# PicoCoffeeMachine_2021-02-28.net
KiCad netlist of a schematic drawn in EasyEDA
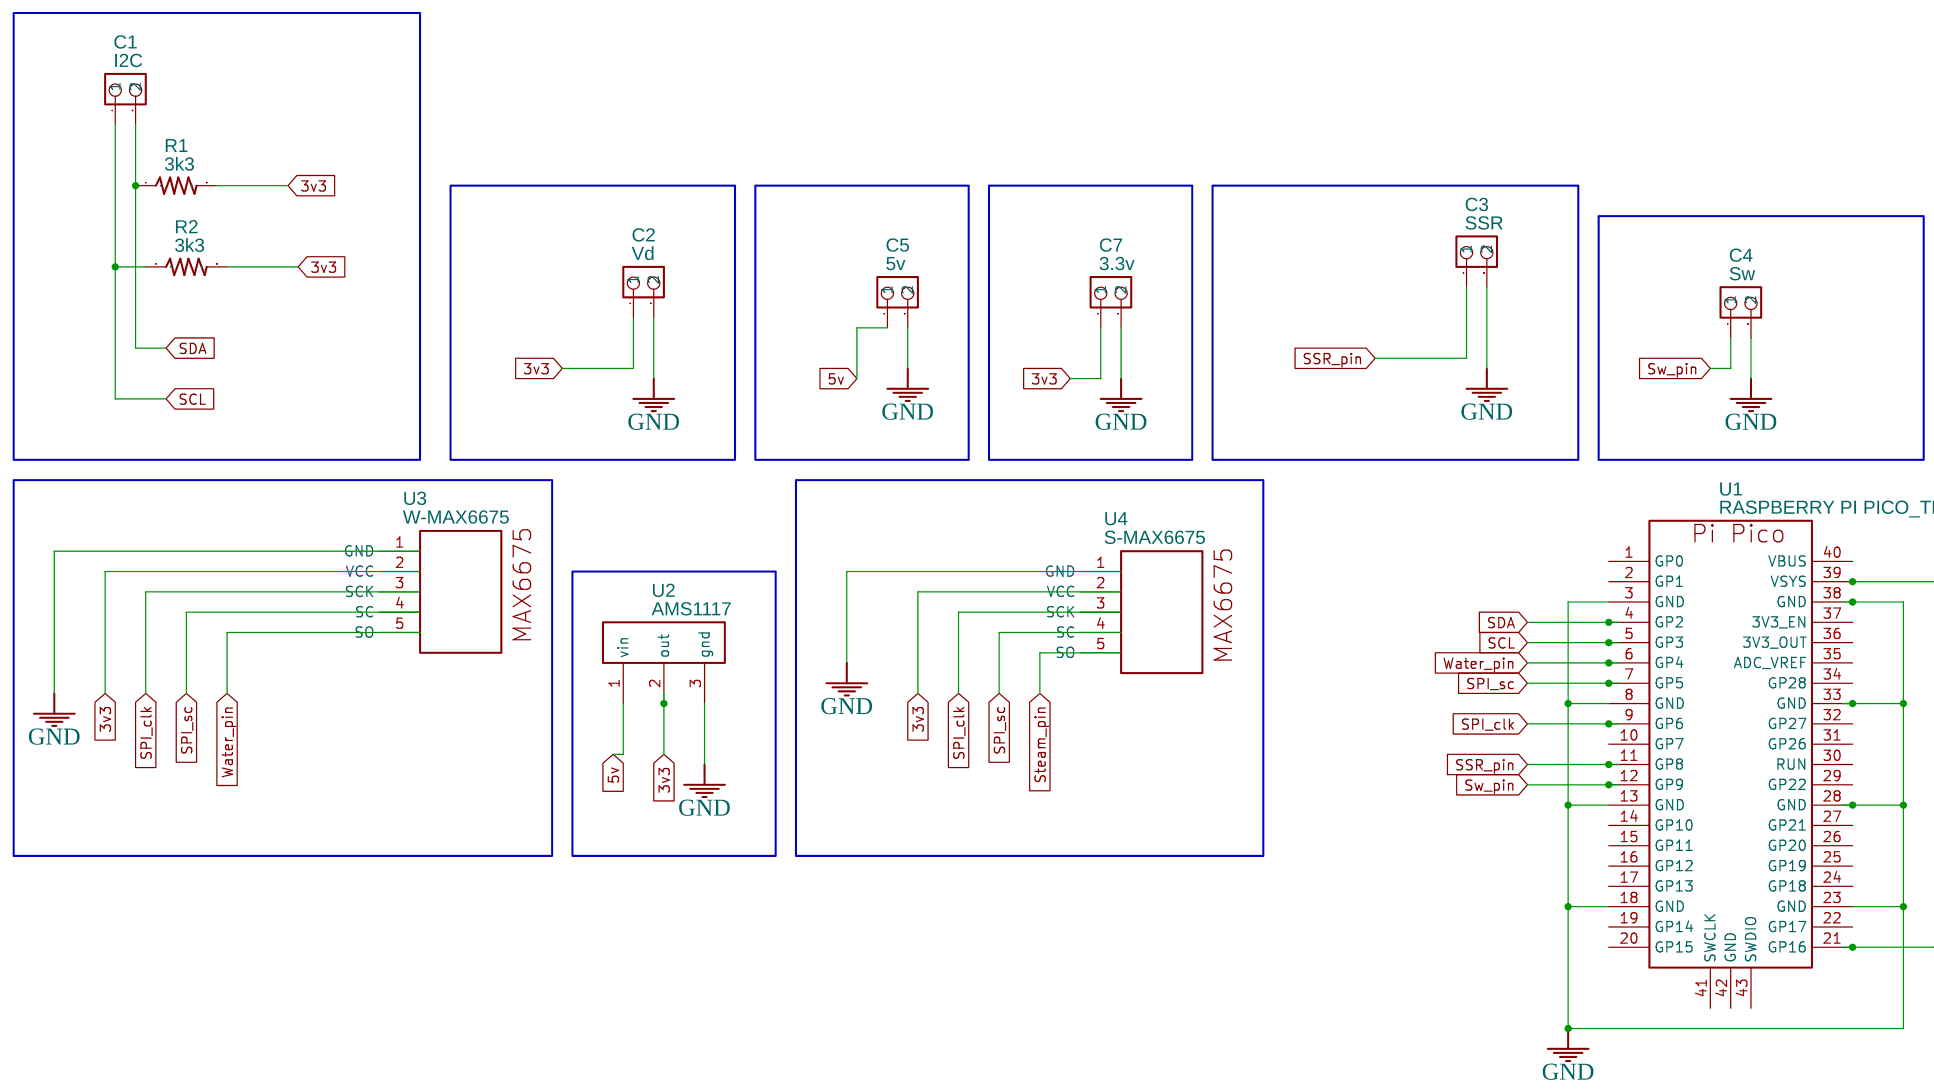
[diagram p0: schematic sheet]

(export (version "E")
  (design (tool "Eeschema 10.0.6"))
  (components
    (comp (ref "C1")
      (value "I2C")
      (fields (field (name "BOM_Manufacturer Part") "XH-2A"))
      (libsource (lib "") (part "JST"))
    )
    (comp (ref "C2")
      (value "Vd")
      (fields (field (name "BOM_Manufacturer Part") "XH-2A"))
      (libsource (lib "") (part "JST"))
    )
    (comp (ref "C3")
      (value "SSR")
      (fields (field (name "BOM_Manufacturer Part") "XH-2A"))
      (libsource (lib "") (part "JST"))
    )
    (comp (ref "C4")
      (value "Sw")
      (fields (field (name "BOM_Manufacturer Part") "XH-2A"))
      (libsource (lib "") (part "JST"))
    )
    (comp (ref "C5")
      (value "5v")
      (fields (field (name "BOM_Manufacturer Part") "XH-2A"))
      (libsource (lib "") (part "JST"))
    )
    (comp (ref "C7")
      (value "3.3v")
      (fields (field (name "BOM_Manufacturer Part") "XH-2A"))
      (libsource (lib "") (part "JST"))
    )
    (comp (ref "R1") (value "3k3") (libsource (lib "") (part "RESISTOR")))
    (comp (ref "R2") (value "3k3") (libsource (lib "") (part "RESISTOR")))
    (comp (ref "U1")
      (value "RASPBERRY PI PICO_THROUGH_HOLE COPY")
      (fields (field (name "BOM_Manufacturer Part") "Pi Pico"))
      (libsource (lib "") (part "RASPBERRY PI PICO_THROUGH_HOLE COPY"))
    )
    (comp (ref "U2") (value "AMS1117") (libsource (lib "") (part "AMS1117")))
    (comp (ref "U3") (value "W-MAX6675") (libsource (lib "") (part "MAX6675")))
    (comp (ref "U4") (value "S-MAX6675") (libsource (lib "") (part "MAX6675")))
  )
  (nets
    (net (code "1") (name "3v3") (class "Default")
      (node (ref "C2") (pin "1") (pinfunction "1_1") (pintype "unspecified"))
      (node (ref "C7") (pin "1") (pinfunction "1_1") (pintype "unspecified"))
      (node (ref "R1") (pin "2") (pinfunction "2_2") (pintype "unspecified"))
      (node (ref "R2") (pin "2") (pinfunction "2_2") (pintype "unspecified"))
      (node (ref "U1") (pin "39") (pinfunction "VSYS_39") (pintype "unspecified"))
      (node (ref "U2") (pin "2") (pinfunction "out_2") (pintype "unspecified"))
      (node (ref "U3") (pin "2") (pinfunction "VCC_2") (pintype "unspecified"))
      (node (ref "U4") (pin "2") (pinfunction "VCC_2") (pintype "unspecified"))
    )
    (net (code "2") (name "5v") (class "Default")
      (node (ref "C5") (pin "1") (pinfunction "1_1") (pintype "unspecified"))
      (node (ref "U2") (pin "1") (pinfunction "vin_1") (pintype "unspecified"))
    )
    (net (code "3") (name "GND") (class "Default")
      (node (ref "C2") (pin "2") (pinfunction "2_2") (pintype "unspecified"))
      (node (ref "C3") (pin "2") (pinfunction "2_2") (pintype "unspecified"))
      (node (ref "C4") (pin "2") (pinfunction "2_2") (pintype "unspecified"))
      (node (ref "C5") (pin "2") (pinfunction "2_2") (pintype "unspecified"))
      (node (ref "C7") (pin "2") (pinfunction "2_2") (pintype "unspecified"))
      (node (ref "U1") (pin "13") (pinfunction "GND_13") (pintype "unspecified"))
      (node (ref "U1") (pin "18") (pinfunction "GND_18") (pintype "unspecified"))
      (node (ref "U1") (pin "23") (pinfunction "GND_23") (pintype "unspecified"))
      (node (ref "U1") (pin "28") (pinfunction "GND_28") (pintype "unspecified"))
      (node (ref "U1") (pin "3") (pinfunction "GND_3") (pintype "unspecified"))
      (node (ref "U1") (pin "33") (pinfunction "GND_33") (pintype "unspecified"))
      (node (ref "U1") (pin "38") (pinfunction "GND_38") (pintype "unspecified"))
      (node (ref "U1") (pin "8") (pinfunction "GND_8") (pintype "unspecified"))
      (node (ref "U2") (pin "3") (pinfunction "gnd_3") (pintype "unspecified"))
      (node (ref "U3") (pin "1") (pinfunction "GND_1") (pintype "unspecified"))
      (node (ref "U4") (pin "1") (pinfunction "GND_1") (pintype "unspecified"))
    )
    (net (code "4") (name "SCL") (class "Default")
      (node (ref "C1") (pin "1") (pinfunction "1_1") (pintype "unspecified"))
      (node (ref "R2") (pin "1") (pinfunction "1_1") (pintype "unspecified"))
      (node (ref "U1") (pin "5") (pinfunction "GP3_5") (pintype "unspecified"))
    )
    (net (code "5") (name "SDA") (class "Default")
      (node (ref "C1") (pin "2") (pinfunction "2_2") (pintype "unspecified"))
      (node (ref "R1") (pin "1") (pinfunction "1_1") (pintype "unspecified"))
      (node (ref "U1") (pin "4") (pinfunction "GP2_4") (pintype "unspecified"))
    )
    (net (code "6") (name "SPI_clk") (class "Default")
      (node (ref "U1") (pin "9") (pinfunction "GP6_9") (pintype "unspecified"))
      (node (ref "U3") (pin "3") (pinfunction "SCK_3") (pintype "unspecified"))
      (node (ref "U4") (pin "3") (pinfunction "SCK_3") (pintype "unspecified"))
    )
    (net (code "7") (name "SPI_sc") (class "Default")
      (node (ref "U1") (pin "7") (pinfunction "GP5_7") (pintype "unspecified"))
      (node (ref "U3") (pin "4") (pinfunction "SC_4") (pintype "unspecified"))
      (node (ref "U4") (pin "4") (pinfunction "SC_4") (pintype "unspecified"))
    )
    (net (code "8") (name "SSR_pin") (class "Default")
      (node (ref "C3") (pin "1") (pinfunction "1_1") (pintype "unspecified"))
      (node (ref "U1") (pin "11") (pinfunction "GP8_11") (pintype "unspecified"))
    )
    (net (code "9") (name "Steam_pin") (class "Default")
      (node (ref "U1") (pin "21") (pinfunction "GP16_21") (pintype "unspecified"))
      (node (ref "U4") (pin "5") (pinfunction "SO_5") (pintype "unspecified"))
    )
    (net (code "10") (name "Sw_pin") (class "Default")
      (node (ref "C4") (pin "1") (pinfunction "1_1") (pintype "unspecified"))
      (node (ref "U1") (pin "12") (pinfunction "GP9_12") (pintype "unspecified"))
    )
    (net (code "11") (name "Water_pin") (class "Default")
      (node (ref "U1") (pin "6") (pinfunction "GP4_6") (pintype "unspecified"))
      (node (ref "U3") (pin "5") (pinfunction "SO_5") (pintype "unspecified"))
    )
    (net (code "12") (name "unconnected-(U1-3V3_EN-Pad37)") (class "Default")
      (node (ref "U1") (pin "37") (pinfunction "3V3_EN_37") (pintype "unspecified"))
    )
    (net (code "13") (name "unconnected-(U1-3V3_OUT-Pad36)") (class "Default")
      (node (ref "U1") (pin "36") (pinfunction "3V3_OUT_36") (pintype "unspecified"))
    )
    (net (code "14") (name "unconnected-(U1-ADC_VREF-Pad35)") (class "Default")
      (node (ref "U1") (pin "35") (pinfunction "ADC_VREF_35") (pintype "unspecified"))
    )
    (net (code "15") (name "unconnected-(U1-GND-Pad42)") (class "Default")
      (node (ref "U1") (pin "42") (pinfunction "GND_42") (pintype "unspecified"))
    )
    (net (code "16") (name "unconnected-(U1-GP0-Pad1)") (class "Default")
      (node (ref "U1") (pin "1") (pinfunction "GP0_1") (pintype "unspecified"))
    )
    (net (code "17") (name "unconnected-(U1-GP1-Pad2)") (class "Default")
      (node (ref "U1") (pin "2") (pinfunction "GP1_2") (pintype "unspecified"))
    )
    (net (code "18") (name "unconnected-(U1-GP7-Pad10)") (class "Default")
      (node (ref "U1") (pin "10") (pinfunction "GP7_10") (pintype "unspecified"))
    )
    (net (code "19") (name "unconnected-(U1-GP10-Pad14)") (class "Default")
      (node (ref "U1") (pin "14") (pinfunction "GP10_14") (pintype "unspecified"))
    )
    (net (code "20") (name "unconnected-(U1-GP11-Pad15)") (class "Default")
      (node (ref "U1") (pin "15") (pinfunction "GP11_15") (pintype "unspecified"))
    )
    (net (code "21") (name "unconnected-(U1-GP12-Pad16)") (class "Default")
      (node (ref "U1") (pin "16") (pinfunction "GP12_16") (pintype "unspecified"))
    )
    (net (code "22") (name "unconnected-(U1-GP13-Pad17)") (class "Default")
      (node (ref "U1") (pin "17") (pinfunction "GP13_17") (pintype "unspecified"))
    )
    (net (code "23") (name "unconnected-(U1-GP14-Pad19)") (class "Default")
      (node (ref "U1") (pin "19") (pinfunction "GP14_19") (pintype "unspecified"))
    )
    (net (code "24") (name "unconnected-(U1-GP15-Pad20)") (class "Default")
      (node (ref "U1") (pin "20") (pinfunction "GP15_20") (pintype "unspecified"))
    )
    (net (code "25") (name "unconnected-(U1-GP17-Pad22)") (class "Default")
      (node (ref "U1") (pin "22") (pinfunction "GP17_22") (pintype "unspecified"))
    )
    (net (code "26") (name "unconnected-(U1-GP18-Pad24)") (class "Default")
      (node (ref "U1") (pin "24") (pinfunction "GP18_24") (pintype "unspecified"))
    )
    (net (code "27") (name "unconnected-(U1-GP19-Pad25)") (class "Default")
      (node (ref "U1") (pin "25") (pinfunction "GP19_25") (pintype "unspecified"))
    )
    (net (code "28") (name "unconnected-(U1-GP20-Pad26)") (class "Default")
      (node (ref "U1") (pin "26") (pinfunction "GP20_26") (pintype "unspecified"))
    )
    (net (code "29") (name "unconnected-(U1-GP21-Pad27)") (class "Default")
      (node (ref "U1") (pin "27") (pinfunction "GP21_27") (pintype "unspecified"))
    )
    (net (code "30") (name "unconnected-(U1-GP22-Pad29)") (class "Default")
      (node (ref "U1") (pin "29") (pinfunction "GP22_29") (pintype "unspecified"))
    )
    (net (code "31") (name "unconnected-(U1-GP26-Pad31)") (class "Default")
      (node (ref "U1") (pin "31") (pinfunction "GP26_31") (pintype "unspecified"))
    )
    (net (code "32") (name "unconnected-(U1-GP27-Pad32)") (class "Default")
      (node (ref "U1") (pin "32") (pinfunction "GP27_32") (pintype "unspecified"))
    )
    (net (code "33") (name "unconnected-(U1-GP28-Pad34)") (class "Default")
      (node (ref "U1") (pin "34") (pinfunction "GP28_34") (pintype "unspecified"))
    )
    (net (code "34") (name "unconnected-(U1-RUN-Pad30)") (class "Default")
      (node (ref "U1") (pin "30") (pinfunction "RUN_30") (pintype "unspecified"))
    )
    (net (code "35") (name "unconnected-(U1-SWCLK-Pad41)") (class "Default")
      (node (ref "U1") (pin "41") (pinfunction "SWCLK_41") (pintype "unspecified"))
    )
    (net (code "36") (name "unconnected-(U1-SWDIO-Pad43)") (class "Default")
      (node (ref "U1") (pin "43") (pinfunction "SWDIO_43") (pintype "unspecified"))
    )
    (net (code "37") (name "unconnected-(U1-VBUS-Pad40)") (class "Default")
      (node (ref "U1") (pin "40") (pinfunction "VBUS_40") (pintype "unspecified"))
    )
  )
)
